# Sheet1.net
KiCad netlist of a schematic drawn in Altium Designer
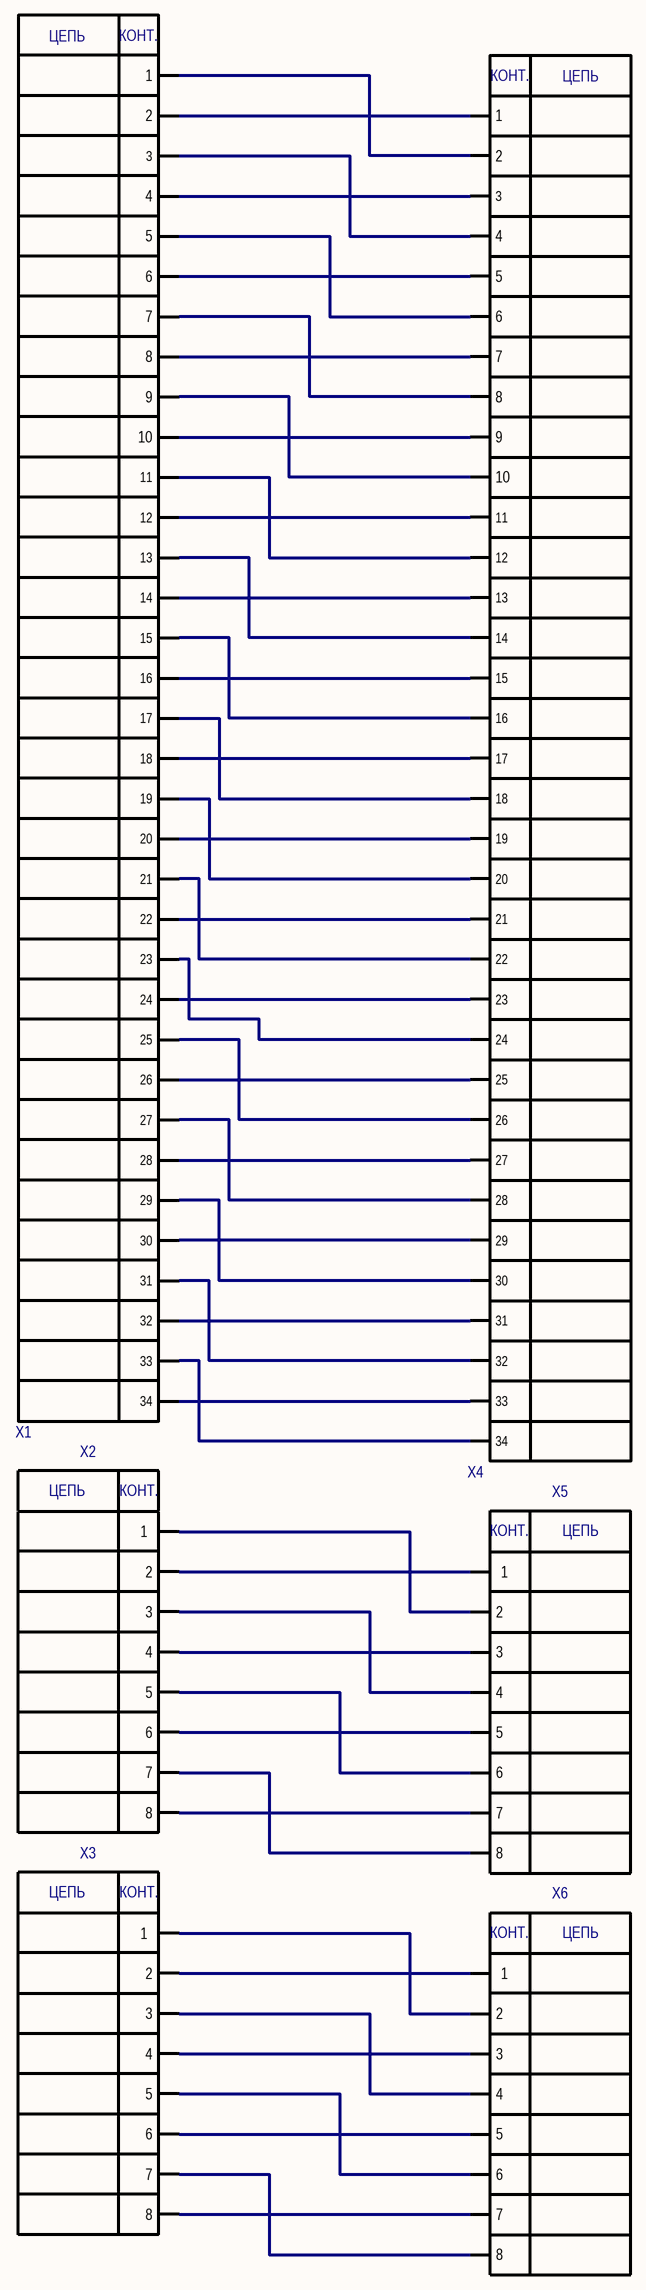
[diagram p0: Sheet1.SchDoc]

(export (version "E")
  (design (tool "Eeschema 10.0.6"))
  (components
    (comp (ref "X1")
      (value "PLD-34")
      (footprint "PLD-34")
      (description "Штыри на плату, шаг 2,54мм, двухрядные")
      (libsource (lib "Connectors") (part "PLD-34"))
    )
    (comp (ref "X2")
      (value "PLD-8")
      (footprint "PLD-8")
      (description "Штыри на плату шаг 2.54мм., двухрядные")
      (fields (field (name "MANUFACTURER") "Бурый Медведь") (field (name "SYMAUTHOR") "Календарова В."))
      (libsource (lib "Connectors") (part "PLD-8"))
    )
    (comp (ref "X3")
      (value "PLD-8")
      (footprint "PLD-8")
      (description "Штыри на плату шаг 2.54мм., двухрядные")
      (fields (field (name "MANUFACTURER") "Бурый Медведь") (field (name "SYMAUTHOR") "Календарова В."))
      (libsource (lib "Connectors") (part "PLD-8"))
    )
    (comp (ref "X4")
      (value "PLD-34")
      (footprint "PLD-34")
      (description "Штыри на плату, шаг 2,54мм, двухрядные")
      (libsource (lib "Connectors") (part "PLD-34"))
    )
    (comp (ref "X5")
      (value "PLD-8")
      (footprint "PLD-8")
      (description "Штыри на плату шаг 2.54мм., двухрядные")
      (fields (field (name "MANUFACTURER") "Бурый Медведь") (field (name "SYMAUTHOR") "Календарова В."))
      (libsource (lib "Connectors") (part "PLD-8"))
    )
    (comp (ref "X6")
      (value "PLD-8")
      (footprint "PLD-8")
      (description "Штыри на плату шаг 2.54мм., двухрядные")
      (fields (field (name "MANUFACTURER") "Бурый Медведь") (field (name "SYMAUTHOR") "Календарова В."))
      (libsource (lib "Connectors") (part "PLD-8"))
    )
  )
  (nets
    (net (code "1") (name "Net-(X1-Pad1)") (class "Default")
      (node (ref "X1") (pin "1") (pinfunction "1_1") (pintype "passive"))
      (node (ref "X4") (pin "2") (pinfunction "2_2") (pintype "passive"))
    )
    (net (code "2") (name "Net-(X1-Pad2)") (class "Default")
      (node (ref "X1") (pin "2") (pinfunction "2_2") (pintype "passive"))
      (node (ref "X4") (pin "1") (pinfunction "1_1") (pintype "passive"))
    )
    (net (code "3") (name "Net-(X1-Pad3)") (class "Default")
      (node (ref "X1") (pin "3") (pinfunction "3_3") (pintype "passive"))
      (node (ref "X4") (pin "4") (pinfunction "4_4") (pintype "passive"))
    )
    (net (code "4") (name "Net-(X1-Pad4)") (class "Default")
      (node (ref "X1") (pin "4") (pinfunction "4_4") (pintype "passive"))
      (node (ref "X4") (pin "3") (pinfunction "3_3") (pintype "passive"))
    )
    (net (code "5") (name "Net-(X1-Pad5)") (class "Default")
      (node (ref "X1") (pin "5") (pinfunction "5_5") (pintype "passive"))
      (node (ref "X4") (pin "6") (pinfunction "6_6") (pintype "passive"))
    )
    (net (code "6") (name "Net-(X1-Pad6)") (class "Default")
      (node (ref "X1") (pin "6") (pinfunction "6_6") (pintype "passive"))
      (node (ref "X4") (pin "5") (pinfunction "5_5") (pintype "passive"))
    )
    (net (code "7") (name "Net-(X1-Pad7)") (class "Default")
      (node (ref "X1") (pin "7") (pinfunction "7_7") (pintype "passive"))
      (node (ref "X4") (pin "8") (pinfunction "8_8") (pintype "passive"))
    )
    (net (code "8") (name "Net-(X1-Pad8)") (class "Default")
      (node (ref "X1") (pin "8") (pinfunction "8_8") (pintype "passive"))
      (node (ref "X4") (pin "7") (pinfunction "7_7") (pintype "passive"))
    )
    (net (code "9") (name "Net-(X1-Pad9)") (class "Default")
      (node (ref "X1") (pin "9") (pinfunction "9_9") (pintype "passive"))
      (node (ref "X4") (pin "10") (pinfunction "10_10") (pintype "passive"))
    )
    (net (code "10") (name "Net-(X1-Pad10)") (class "Default")
      (node (ref "X1") (pin "10") (pinfunction "10_10") (pintype "passive"))
      (node (ref "X4") (pin "9") (pinfunction "9_9") (pintype "passive"))
    )
    (net (code "11") (name "Net-(X1-Pad11)") (class "Default")
      (node (ref "X1") (pin "11") (pinfunction "11_11") (pintype "passive"))
      (node (ref "X4") (pin "12") (pinfunction "12_12") (pintype "passive"))
    )
    (net (code "12") (name "Net-(X1-Pad12)") (class "Default")
      (node (ref "X1") (pin "12") (pinfunction "12_12") (pintype "passive"))
      (node (ref "X4") (pin "11") (pinfunction "11_11") (pintype "passive"))
    )
    (net (code "13") (name "Net-(X1-Pad13)") (class "Default")
      (node (ref "X1") (pin "13") (pinfunction "13_13") (pintype "passive"))
      (node (ref "X4") (pin "14") (pinfunction "14_14") (pintype "passive"))
    )
    (net (code "14") (name "Net-(X1-Pad14)") (class "Default")
      (node (ref "X1") (pin "14") (pinfunction "14_14") (pintype "passive"))
      (node (ref "X4") (pin "13") (pinfunction "13_13") (pintype "passive"))
    )
    (net (code "15") (name "Net-(X1-Pad15)") (class "Default")
      (node (ref "X1") (pin "15") (pinfunction "15_15") (pintype "passive"))
      (node (ref "X4") (pin "16") (pinfunction "16_16") (pintype "passive"))
    )
    (net (code "16") (name "Net-(X1-Pad16)") (class "Default")
      (node (ref "X1") (pin "16") (pinfunction "16_16") (pintype "passive"))
      (node (ref "X4") (pin "15") (pinfunction "15_15") (pintype "passive"))
    )
    (net (code "17") (name "Net-(X1-Pad17)") (class "Default")
      (node (ref "X1") (pin "17") (pinfunction "17_17") (pintype "passive"))
      (node (ref "X4") (pin "18") (pinfunction "18_18") (pintype "passive"))
    )
    (net (code "18") (name "Net-(X1-Pad18)") (class "Default")
      (node (ref "X1") (pin "18") (pinfunction "18_18") (pintype "passive"))
      (node (ref "X4") (pin "17") (pinfunction "17_17") (pintype "passive"))
    )
    (net (code "19") (name "Net-(X1-Pad19)") (class "Default")
      (node (ref "X1") (pin "19") (pinfunction "19_19") (pintype "passive"))
      (node (ref "X4") (pin "20") (pinfunction "20_20") (pintype "passive"))
    )
    (net (code "20") (name "Net-(X1-Pad20)") (class "Default")
      (node (ref "X1") (pin "20") (pinfunction "20_20") (pintype "passive"))
      (node (ref "X4") (pin "19") (pinfunction "19_19") (pintype "passive"))
    )
    (net (code "21") (name "Net-(X1-Pad21)") (class "Default")
      (node (ref "X1") (pin "21") (pinfunction "21_21") (pintype "passive"))
      (node (ref "X4") (pin "22") (pinfunction "22_22") (pintype "passive"))
    )
    (net (code "22") (name "Net-(X1-Pad22)") (class "Default")
      (node (ref "X1") (pin "22") (pinfunction "22_22") (pintype "passive"))
      (node (ref "X4") (pin "21") (pinfunction "21_21") (pintype "passive"))
    )
    (net (code "23") (name "Net-(X1-Pad23)") (class "Default")
      (node (ref "X1") (pin "23") (pinfunction "23_23") (pintype "passive"))
      (node (ref "X4") (pin "24") (pinfunction "24_24") (pintype "passive"))
    )
    (net (code "24") (name "Net-(X1-Pad24)") (class "Default")
      (node (ref "X1") (pin "24") (pinfunction "24_24") (pintype "passive"))
      (node (ref "X4") (pin "23") (pinfunction "23_23") (pintype "passive"))
    )
    (net (code "25") (name "Net-(X1-Pad25)") (class "Default")
      (node (ref "X1") (pin "25") (pinfunction "25_25") (pintype "passive"))
      (node (ref "X4") (pin "26") (pinfunction "26_26") (pintype "passive"))
    )
    (net (code "26") (name "Net-(X1-Pad26)") (class "Default")
      (node (ref "X1") (pin "26") (pinfunction "26_26") (pintype "passive"))
      (node (ref "X4") (pin "25") (pinfunction "25_25") (pintype "passive"))
    )
    (net (code "27") (name "Net-(X1-Pad27)") (class "Default")
      (node (ref "X1") (pin "27") (pinfunction "27_27") (pintype "passive"))
      (node (ref "X4") (pin "28") (pinfunction "28_28") (pintype "passive"))
    )
    (net (code "28") (name "Net-(X1-Pad28)") (class "Default")
      (node (ref "X1") (pin "28") (pinfunction "28_28") (pintype "passive"))
      (node (ref "X4") (pin "27") (pinfunction "27_27") (pintype "passive"))
    )
    (net (code "29") (name "Net-(X1-Pad29)") (class "Default")
      (node (ref "X1") (pin "29") (pinfunction "29_29") (pintype "passive"))
      (node (ref "X4") (pin "30") (pinfunction "30_30") (pintype "passive"))
    )
    (net (code "30") (name "Net-(X1-Pad30)") (class "Default")
      (node (ref "X1") (pin "30") (pinfunction "30_30") (pintype "passive"))
      (node (ref "X4") (pin "29") (pinfunction "29_29") (pintype "passive"))
    )
    (net (code "31") (name "Net-(X1-Pad31)") (class "Default")
      (node (ref "X1") (pin "31") (pinfunction "31_31") (pintype "passive"))
      (node (ref "X4") (pin "32") (pinfunction "32_32") (pintype "passive"))
    )
    (net (code "32") (name "Net-(X1-Pad32)") (class "Default")
      (node (ref "X1") (pin "32") (pinfunction "32_32") (pintype "passive"))
      (node (ref "X4") (pin "31") (pinfunction "31_31") (pintype "passive"))
    )
    (net (code "33") (name "Net-(X1-Pad33)") (class "Default")
      (node (ref "X1") (pin "33") (pinfunction "33_33") (pintype "passive"))
      (node (ref "X4") (pin "34") (pinfunction "34_34") (pintype "passive"))
    )
    (net (code "34") (name "Net-(X1-Pad34)") (class "Default")
      (node (ref "X1") (pin "34") (pinfunction "34_34") (pintype "passive"))
      (node (ref "X4") (pin "33") (pinfunction "33_33") (pintype "passive"))
    )
    (net (code "35") (name "Net-(X2-Pad1)") (class "Default")
      (node (ref "X2") (pin "1") (pinfunction "1_1") (pintype "passive"))
      (node (ref "X5") (pin "2") (pinfunction "2_2") (pintype "passive"))
    )
    (net (code "36") (name "Net-(X2-Pad2)") (class "Default")
      (node (ref "X2") (pin "2") (pinfunction "2_2") (pintype "passive"))
      (node (ref "X5") (pin "1") (pinfunction "1_1") (pintype "passive"))
    )
    (net (code "37") (name "Net-(X2-Pad3)") (class "Default")
      (node (ref "X2") (pin "3") (pinfunction "3_3") (pintype "passive"))
      (node (ref "X5") (pin "4") (pinfunction "4_4") (pintype "passive"))
    )
    (net (code "38") (name "Net-(X2-Pad4)") (class "Default")
      (node (ref "X2") (pin "4") (pinfunction "4_4") (pintype "passive"))
      (node (ref "X5") (pin "3") (pinfunction "3_3") (pintype "passive"))
    )
    (net (code "39") (name "Net-(X2-Pad5)") (class "Default")
      (node (ref "X2") (pin "5") (pinfunction "5_5") (pintype "passive"))
      (node (ref "X5") (pin "6") (pinfunction "6_6") (pintype "passive"))
    )
    (net (code "40") (name "Net-(X2-Pad6)") (class "Default")
      (node (ref "X2") (pin "6") (pinfunction "6_6") (pintype "passive"))
      (node (ref "X5") (pin "5") (pinfunction "5_5") (pintype "passive"))
    )
    (net (code "41") (name "Net-(X2-Pad7)") (class "Default")
      (node (ref "X2") (pin "7") (pinfunction "7_7") (pintype "passive"))
      (node (ref "X5") (pin "8") (pinfunction "8_8") (pintype "passive"))
    )
    (net (code "42") (name "Net-(X2-Pad8)") (class "Default")
      (node (ref "X2") (pin "8") (pinfunction "8_8") (pintype "passive"))
      (node (ref "X5") (pin "7") (pinfunction "7_7") (pintype "passive"))
    )
    (net (code "43") (name "Net-(X3-Pad1)") (class "Default")
      (node (ref "X3") (pin "1") (pinfunction "1_1") (pintype "passive"))
      (node (ref "X6") (pin "2") (pinfunction "2_2") (pintype "passive"))
    )
    (net (code "44") (name "Net-(X3-Pad2)") (class "Default")
      (node (ref "X3") (pin "2") (pinfunction "2_2") (pintype "passive"))
      (node (ref "X6") (pin "1") (pinfunction "1_1") (pintype "passive"))
    )
    (net (code "45") (name "Net-(X3-Pad3)") (class "Default")
      (node (ref "X3") (pin "3") (pinfunction "3_3") (pintype "passive"))
      (node (ref "X6") (pin "4") (pinfunction "4_4") (pintype "passive"))
    )
    (net (code "46") (name "Net-(X3-Pad4)") (class "Default")
      (node (ref "X3") (pin "4") (pinfunction "4_4") (pintype "passive"))
      (node (ref "X6") (pin "3") (pinfunction "3_3") (pintype "passive"))
    )
    (net (code "47") (name "Net-(X3-Pad5)") (class "Default")
      (node (ref "X3") (pin "5") (pinfunction "5_5") (pintype "passive"))
      (node (ref "X6") (pin "6") (pinfunction "6_6") (pintype "passive"))
    )
    (net (code "48") (name "Net-(X3-Pad6)") (class "Default")
      (node (ref "X3") (pin "6") (pinfunction "6_6") (pintype "passive"))
      (node (ref "X6") (pin "5") (pinfunction "5_5") (pintype "passive"))
    )
    (net (code "49") (name "Net-(X3-Pad7)") (class "Default")
      (node (ref "X3") (pin "7") (pinfunction "7_7") (pintype "passive"))
      (node (ref "X6") (pin "8") (pinfunction "8_8") (pintype "passive"))
    )
    (net (code "50") (name "Net-(X3-Pad8)") (class "Default")
      (node (ref "X3") (pin "8") (pinfunction "8_8") (pintype "passive"))
      (node (ref "X6") (pin "7") (pinfunction "7_7") (pintype "passive"))
    )
  )
)
